# Fourier.net
KiCad netlist of a schematic drawn in Altium Designer
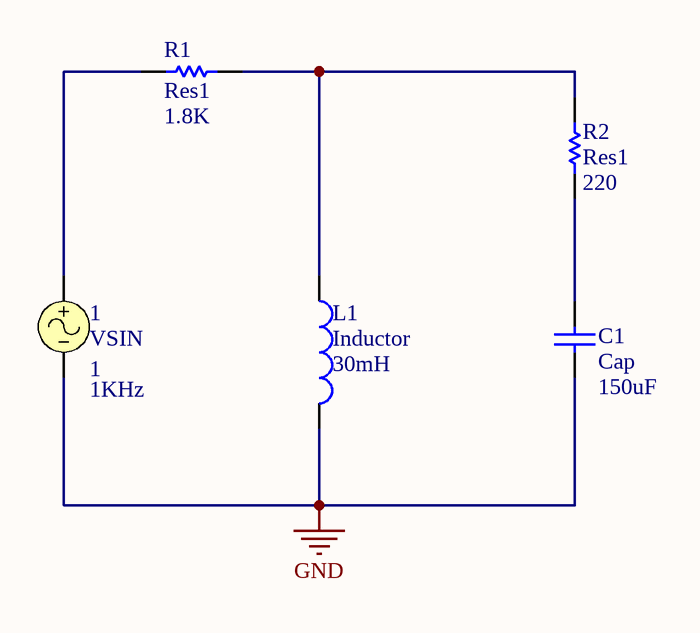
[diagram p0: Fourier.SchDoc]

(export (version "E")
  (design (tool "Eeschema 10.0.6"))
  (components
    (comp (ref "1")
      (value "VSIN")
      (description "Sinusoidal Voltage Source")
      (fields
        (field (name "AMPLITUDE") "1")
        (field (name "FREQUENCY") "1KHz")
        (field (name "PUBLISHER") "Altium Limited")
      )
      (libsource (lib "Simulation Sources") (part "VSIN"))
    )
    (comp (ref "C1")
      (value "Cap")
      (footprint "RAD-0.3")
      (description "Capacitor")
      (fields (field (name "ALTIUM_VALUE") "150uF") (field (name "PUBLISHER") "Altium Limited"))
      (libsource (lib "Miscellaneous Devices") (part "Cap"))
    )
    (comp (ref "L1")
      (value "Inductor")
      (footprint "0402-A")
      (fields (field (name "ALTIUM_VALUE") "30mH") (field (name "PUBLISHER") "Altium Limited"))
      (libsource (lib "Miscellaneous Devices") (part "Inductor"))
    )
    (comp (ref "R1")
      (value "Res1")
      (footprint "AXIAL-0.3")
      (description "Resistor")
      (fields (field (name "ALTIUM_VALUE") "1.8K") (field (name "PUBLISHER") "Altium Limited"))
      (libsource (lib "Miscellaneous Devices") (part "Res1"))
    )
    (comp (ref "R2")
      (value "Res1")
      (footprint "AXIAL-0.3")
      (description "Resistor")
      (fields (field (name "ALTIUM_VALUE") "220") (field (name "PUBLISHER") "Altium Limited"))
      (libsource (lib "Miscellaneous Devices") (part "Res1"))
    )
  )
  (nets
    (net (code "1") (name "GND") (class "Default")
      (node (ref "1") (pin "2") (pinfunction "2_2") (pintype "passive"))
      (node (ref "C1") (pin "1") (pinfunction "1_1") (pintype "passive"))
      (node (ref "L1") (pin "2") (pinfunction "2_2") (pintype "passive"))
    )
    (net (code "2") (name "Net-(1-Pad1)") (class "Default")
      (node (ref "1") (pin "1") (pinfunction "1_1") (pintype "passive"))
      (node (ref "R1") (pin "1") (pinfunction "1_1") (pintype "passive"))
    )
    (net (code "3") (name "Net-(C1-Pad2)") (class "Default")
      (node (ref "C1") (pin "2") (pinfunction "2_2") (pintype "passive"))
      (node (ref "R2") (pin "2") (pinfunction "2_2") (pintype "passive"))
    )
    (net (code "4") (name "Net-(L1-Pad1)") (class "Default")
      (node (ref "L1") (pin "1") (pinfunction "1_1") (pintype "passive"))
      (node (ref "R1") (pin "2") (pinfunction "2_2") (pintype "passive"))
      (node (ref "R2") (pin "1") (pinfunction "1_1") (pintype "passive"))
    )
  )
)
